# 01_POWER.net
KiCad netlist of a schematic drawn in Altium Designer
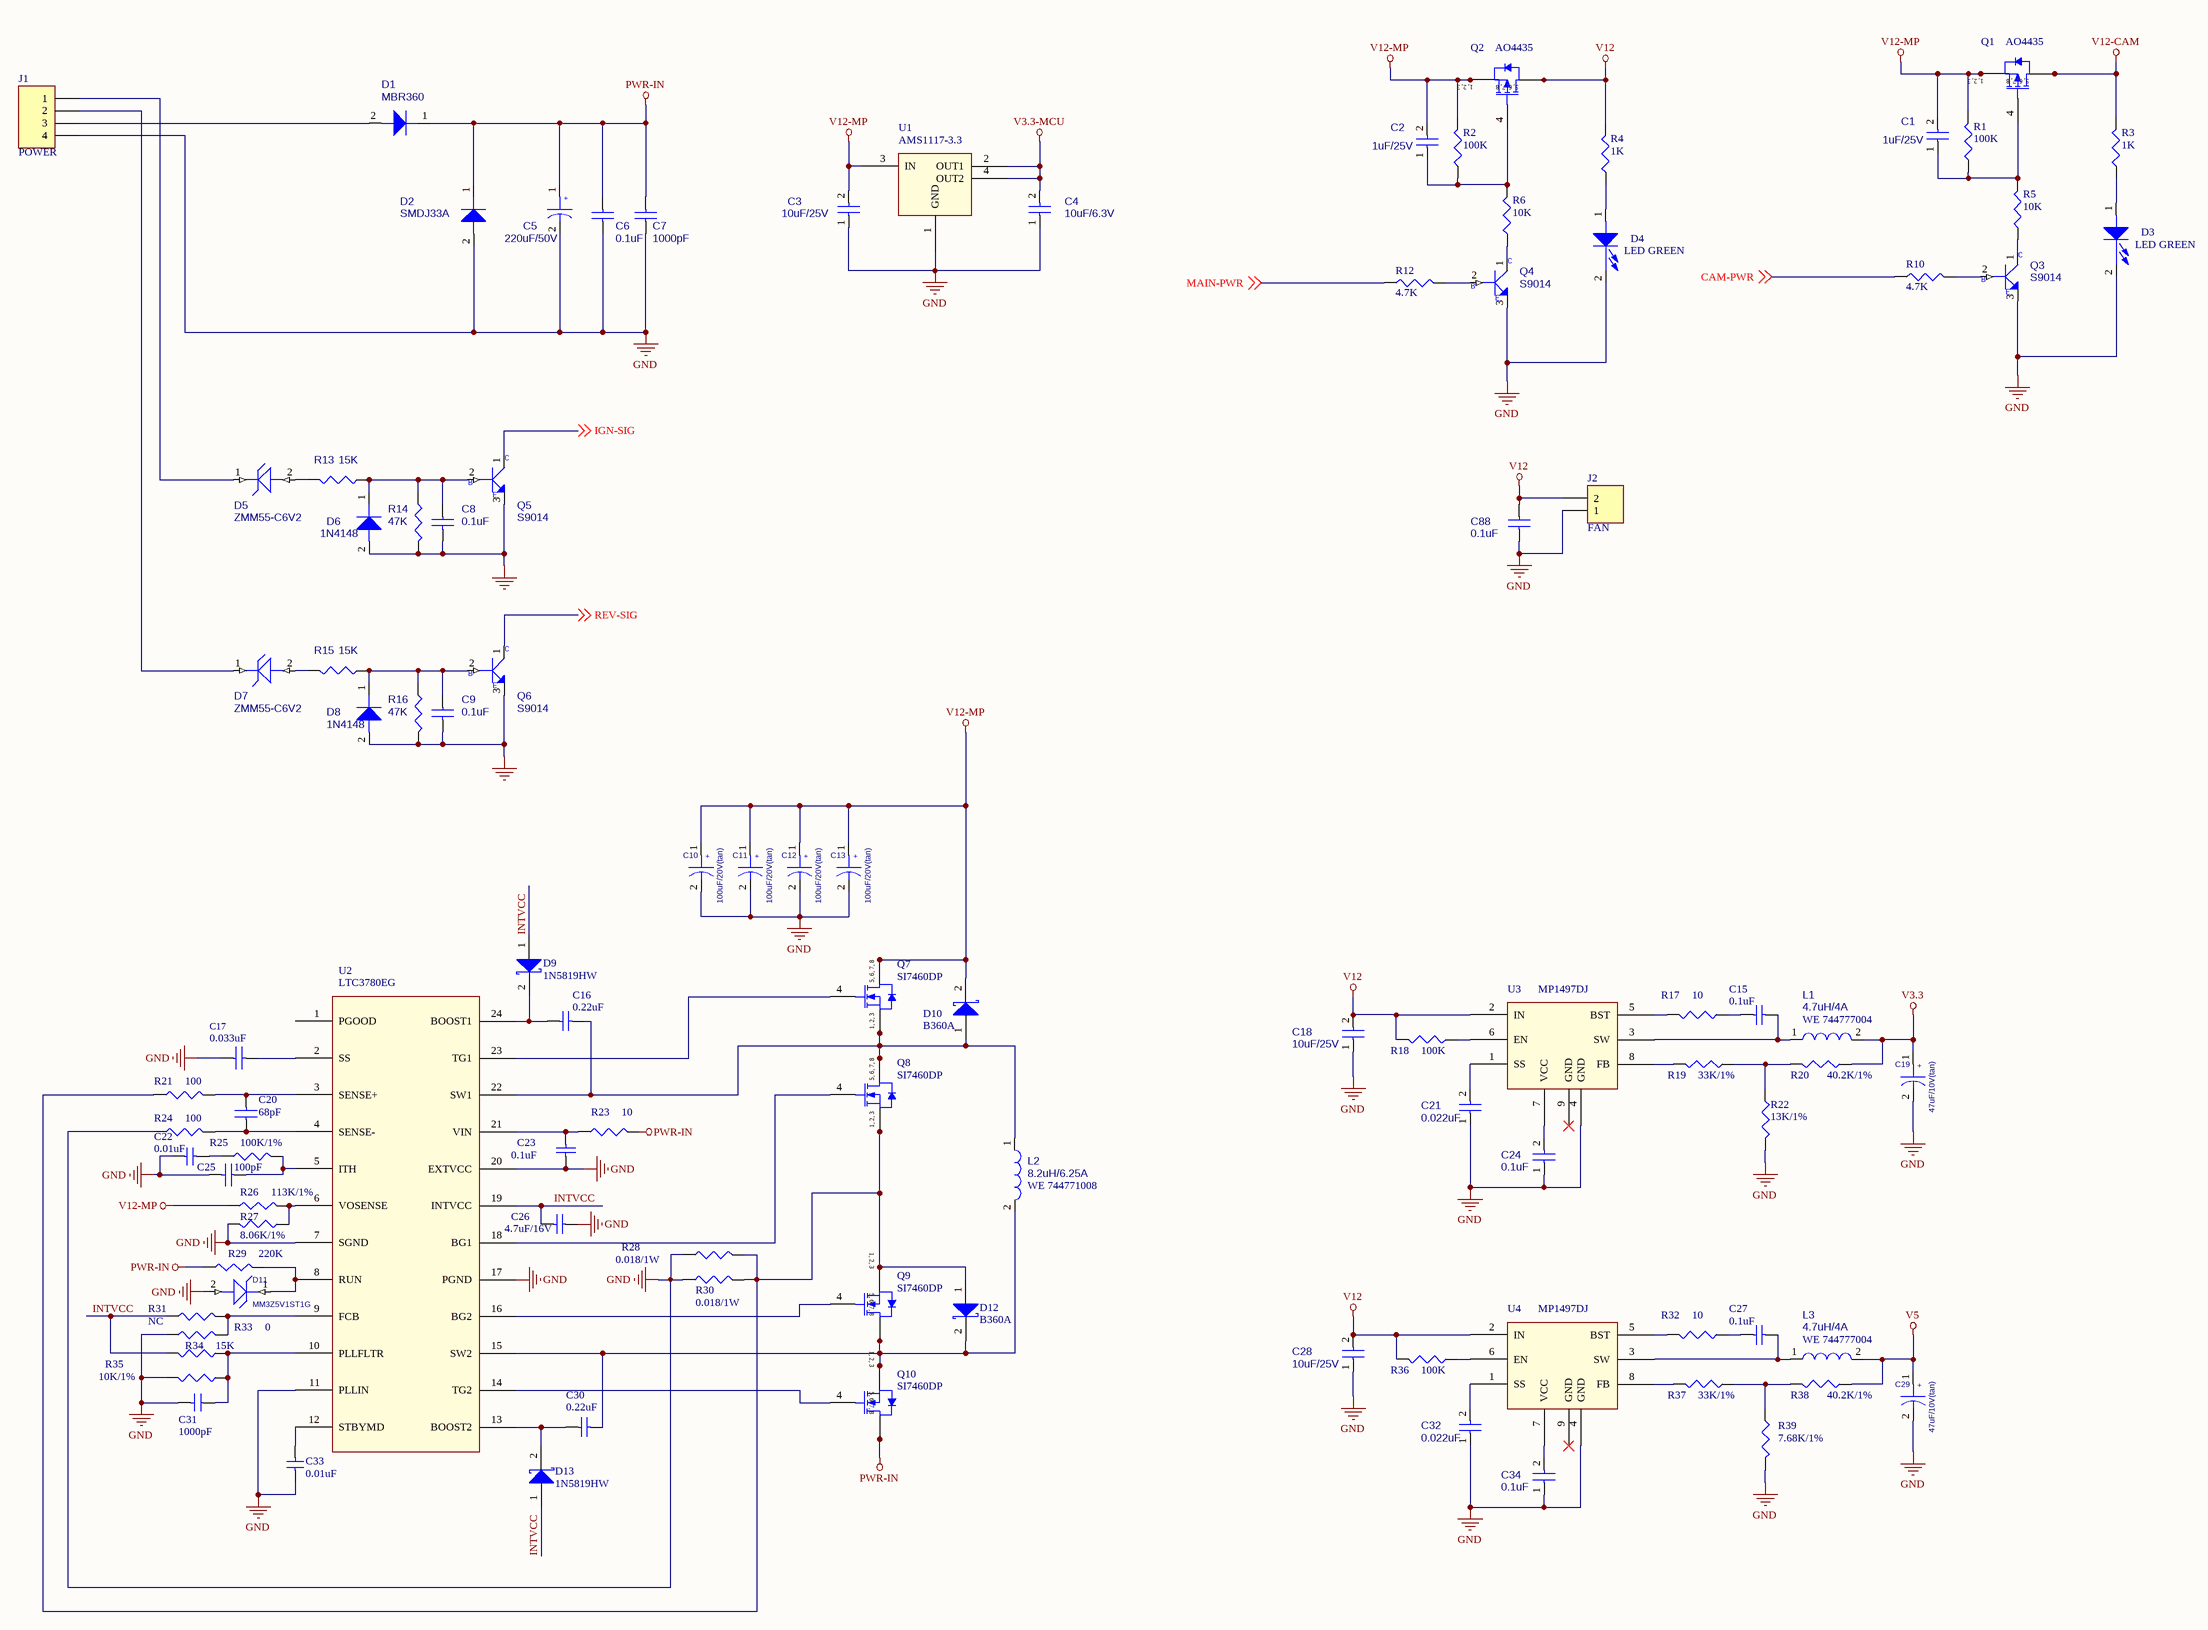
[diagram p0: [01]POWER.SchDoc]

(export (version "E")
  (design (tool "Eeschema 10.0.6"))
  (components
    (comp (ref "C1") (value "1uF/25V") (footprint "0805") (libsource (lib "*") (part "CAP NP_Dup2")))
    (comp (ref "C2") (value "1uF/25V") (footprint "0805") (libsource (lib "*") (part "CAP NP_Dup2")))
    (comp (ref "C3") (value "10uF/25V") (footprint "1812") (libsource (lib "*") (part "CAP NP_Dup2")))
    (comp (ref "C4") (value "10uF/6.3V") (footprint "0805") (libsource (lib "*") (part "CAP NP_Dup2")))
    (comp (ref "C5") (value "220uF/50V") (libsource (lib "*") (part "CAP WP")))
    (comp (ref "C6") (value "0.1uF") (libsource (lib "") (part "CAP NP_Dup2_1")))
    (comp (ref "C7") (value "1000pF") (libsource (lib "") (part "CAP NP_Dup2_1")))
    (comp (ref "C8") (value "0.1uF") (libsource (lib "*") (part "CAP")))
    (comp (ref "C9") (value "0.1uF") (libsource (lib "*") (part "CAP")))
    (comp (ref "C10") (value "100uF/20V(tan)") (footprint "7343") (libsource (lib "*") (part "CAP WP")))
    (comp (ref "C11") (value "100uF/20V(tan)") (footprint "7343") (libsource (lib "*") (part "CAP WP")))
    (comp (ref "C12") (value "100uF/20V(tan)") (footprint "7343") (libsource (lib "*") (part "CAP WP")))
    (comp (ref "C13") (value "100uF/20V(tan)") (footprint "7343") (libsource (lib "*") (part "CAP WP")))
    (comp (ref "C15")
      (value "0.1uF")
      (footprint "0603")
      (description "Capacitor")
      (libsource (lib "Miscellaneous Devices") (part "Cap"))
    )
    (comp (ref "C16")
      (value "0.22uF")
      (footprint "0603")
      (description "Capacitor")
      (libsource (lib "Miscellaneous Devices") (part "Cap"))
    )
    (comp (ref "C17") (value "0.033uF") (footprint "0603") (libsource (lib "*") (part "06033C223KAT1A_0")))
    (comp (ref "C18") (value "10uF/25V") (footprint "1812") (libsource (lib "*") (part "CAP NP_Dup2")))
    (comp (ref "C19") (value "47uF/10V(tan)") (footprint "3528") (libsource (lib "*") (part "CAP WP")))
    (comp (ref "C20") (value "68pF") (footprint "0603") (libsource (lib "*") (part "06033C223KAT1A_0")))
    (comp (ref "C21") (value "0.022uF") (footprint "0603") (libsource (lib "*") (part "CAP NP_Dup2")))
    (comp (ref "C22") (value "0.01uF") (footprint "0603") (libsource (lib "*") (part "06033C103KAT2A")))
    (comp (ref "C23")
      (value "0.1uF")
      (footprint "0603")
      (description "Capacitor")
      (libsource (lib "Miscellaneous Devices") (part "Cap"))
    )
    (comp (ref "C24") (value "0.1uF") (footprint "0603") (libsource (lib "*") (part "CAP NP_Dup2")))
    (comp (ref "C25") (value "100pF") (footprint "0603") (libsource (lib "*") (part "06035A470KAT1A_0")))
    (comp (ref "C26")
      (value "4.7uF/16V")
      (footprint "0805")
      (description "Capacitor")
      (libsource (lib "Miscellaneous Devices") (part "Cap"))
    )
    (comp (ref "C27")
      (value "0.1uF")
      (footprint "0603")
      (description "Capacitor")
      (libsource (lib "Miscellaneous Devices") (part "Cap"))
    )
    (comp (ref "C28") (value "10uF/25V") (footprint "1812") (libsource (lib "*") (part "CAP NP_Dup2")))
    (comp (ref "C29") (value "47uF/10V(tan)") (footprint "3528") (libsource (lib "*") (part "CAP WP")))
    (comp (ref "C30")
      (value "0.22uF")
      (footprint "0603")
      (description "Capacitor")
      (libsource (lib "Miscellaneous Devices") (part "Cap"))
    )
    (comp (ref "C31") (value "1000pF") (footprint "0603") (libsource (lib "*") (part "06033C103KAT2A_0")))
    (comp (ref "C32") (value "0.022uF") (footprint "0603") (libsource (lib "*") (part "CAP NP_Dup2")))
    (comp (ref "C33") (value "0.01uF") (footprint "0603") (libsource (lib "*") (part "06033C103KAT2A_0")))
    (comp (ref "C34") (value "0.1uF") (footprint "0603") (libsource (lib "*") (part "CAP NP_Dup2")))
    (comp (ref "C88") (value "0.1uF") (libsource (lib "") (part "CAP NP_Dup2_1")))
    (comp (ref "D1")
      (value "MBR360")
      (footprint "DO214AB")
      (libsource (lib "*") (part "1N4148WS-7-F_SOD323-2"))
    )
    (comp (ref "D2")
      (value "SMDJ33A")
      (footprint "DO214AB")
      (libsource (lib "*") (part "1N4148WS-7-F_SOD323-2"))
    )
    (comp (ref "D3") (value "LED GREEN") (footprint "LED0603") (libsource (lib "*") (part "LN01401_1")))
    (comp (ref "D4") (value "LED GREEN") (footprint "LED0603") (libsource (lib "*") (part "LN01401_1")))
    (comp (ref "D5")
      (value "ZMM55-C6V2")
      (footprint "MINI-MELF")
      (libsource (lib "*") (part "MMGZ5231BPTLL34"))
    )
    (comp (ref "D6")
      (value "1N4148")
      (footprint "MINI-MELF")
      (libsource (lib "*") (part "1N4148WS-7-F_SOD323-2"))
    )
    (comp (ref "D7")
      (value "ZMM55-C6V2")
      (footprint "MINI-MELF")
      (libsource (lib "*") (part "MMGZ5231BPTLL34"))
    )
    (comp (ref "D8")
      (value "1N4148")
      (footprint "MINI-MELF")
      (libsource (lib "*") (part "1N4148WS-7-F_SOD323-2"))
    )
    (comp (ref "D9")
      (value "1N5819HW")
      (footprint "1N5819")
      (description "Schottky Rectifier")
      (libsource (lib "Miscellaneous Devices") (part "Diode 11DQ03"))
    )
    (comp (ref "D10")
      (value "B360A")
      (footprint "B320A")
      (description "Schottky Rectifier")
      (libsource (lib "Miscellaneous Devices") (part "Diode 11DQ03"))
    )
    (comp (ref "D11")
      (value "MM3Z5V1ST1G")
      (footprint "MM3Z5V1ST1G")
      (libsource (lib "*") (part "MMGZ5231BPTLL34"))
    )
    (comp (ref "D12")
      (value "B360A")
      (footprint "B320A")
      (description "Schottky Rectifier")
      (libsource (lib "Miscellaneous Devices") (part "Diode 11DQ03"))
    )
    (comp (ref "D13")
      (value "1N5819HW")
      (footprint "1N5819")
      (description "Schottky Rectifier")
      (libsource (lib "Miscellaneous Devices") (part "Diode 11DQ03"))
    )
    (comp (ref "J1")
      (value "POWER")
      (footprint "5557-4PIN")
      (description "Header, 4-Pin")
      (libsource (lib "Miscellaneous Connectors") (part "Header 4"))
    )
    (comp (ref "J2")
      (value "FAN")
      (footprint "XH2.0-2P-SMD")
      (description "Header, 2-Pin")
      (fields (field (name "PUBLISHER") "Altium Limited"))
      (libsource (lib "Miscellaneous Connectors") (part "Header 2"))
    )
    (comp (ref "L1")
      (value "4.7uH/4A")
      (footprint "IND-4.7UH-4A")
      (fields (field (name "CODE") "WE 744777004"))
      (libsource (lib "*") (part "4.7UH_CDH2D09BNP-4R7MC_0.7A_20%"))
    )
    (comp (ref "L2")
      (value "8.2uH/6.25A")
      (footprint "IND-8.2UH-10A")
      (fields (field (name "CODE") "WE 744771008"))
      (libsource (lib "*") (part "4.7UH_CDH2D09BNP-4R7MC_0.7A_20%"))
    )
    (comp (ref "L3")
      (value "4.7uH/4A")
      (footprint "IND-4.7UH-4A")
      (fields (field (name "CODE") "WE 744777004"))
      (libsource (lib "*") (part "4.7UH_CDH2D09BNP-4R7MC_0.7A_20%"))
    )
    (comp (ref "Q1")
      (value "AO4435")
      (footprint "SO8")
      (description "P-Channel 30V (D-S)  MOSFET")
      (fields (field (name "PUBLISHER") "Altium Limited"))
      (libsource (lib "Vishay Siliconix Discrete MOSFET") (part "SI4431DY"))
    )
    (comp (ref "Q2")
      (value "AO4435")
      (footprint "SO8")
      (description "P-Channel 30V (D-S)  MOSFET")
      (fields (field (name "PUBLISHER") "Altium Limited"))
      (libsource (lib "Vishay Siliconix Discrete MOSFET") (part "SI4431DY"))
    )
    (comp (ref "Q3")
      (value "S9014")
      (footprint "NPN")
      (fields (field (name "PART NUMBER") "SB039040000"))
      (libsource (lib "*") (part "MMBT3904_NL_SOT23-3"))
    )
    (comp (ref "Q4")
      (value "S9014")
      (footprint "NPN")
      (fields (field (name "PART NUMBER") "SB039040000"))
      (libsource (lib "*") (part "MMBT3904_NL_SOT23-3"))
    )
    (comp (ref "Q5")
      (value "S9014")
      (footprint "NPN")
      (fields (field (name "PART NUMBER") "SB039040000"))
      (libsource (lib "*") (part "MMBT3904_NL_SOT23-3"))
    )
    (comp (ref "Q6") (value "S9014") (footprint "NPN") (libsource (lib "*") (part "MMBT3904_NL_SOT23-3")))
    (comp (ref "Q7")
      (value "SI7460DP")
      (footprint "POWERPAK")
      (description "N-Channel 30V (D-S)  MOSFET")
      (libsource (lib "Vishay Siliconix Discrete MOSFET") (part "SI4410DY"))
    )
    (comp (ref "Q8")
      (value "SI7460DP")
      (footprint "POWERPAK")
      (description "N-Channel 30V (D-S)  MOSFET")
      (libsource (lib "Vishay Siliconix Discrete MOSFET") (part "SI4410DY"))
    )
    (comp (ref "Q9")
      (value "SI7460DP")
      (footprint "POWERPAK")
      (description "N-Channel 30V (D-S)  MOSFET")
      (libsource (lib "Vishay Siliconix Discrete MOSFET") (part "SI4410DY"))
    )
    (comp (ref "Q10")
      (value "SI7460DP")
      (footprint "POWERPAK")
      (description "N-Channel 30V (D-S)  MOSFET")
      (libsource (lib "Vishay Siliconix Discrete MOSFET") (part "SI4410DY"))
    )
    (comp (ref "R1") (value "100K") (footprint "0603") (libsource (lib "*") (part "CR16-1003FM")))
    (comp (ref "R2") (value "100K") (footprint "0603") (libsource (lib "*") (part "CR16-1003FM")))
    (comp (ref "R3") (value "1K") (footprint "0603") (libsource (lib "*") (part "CR16-1003FM")))
    (comp (ref "R4") (value "1K") (footprint "0603") (libsource (lib "*") (part "CR16-1003FM")))
    (comp (ref "R5") (value "10K") (footprint "0603") (libsource (lib "*") (part "CR16-1003FM")))
    (comp (ref "R6") (value "10K") (footprint "0603") (libsource (lib "*") (part "CR16-1003FM")))
    (comp (ref "R10") (value "4.7K") (footprint "0603") (libsource (lib "*") (part "CR16-1003FM")))
    (comp (ref "R12") (value "4.7K") (footprint "0603") (libsource (lib "*") (part "CR16-1003FM")))
    (comp (ref "R13") (value "15K") (libsource (lib "*") (part "R")))
    (comp (ref "R14") (value "47K") (libsource (lib "*") (part "R")))
    (comp (ref "R15") (value "15K") (libsource (lib "*") (part "R")))
    (comp (ref "R16") (value "47K") (libsource (lib "*") (part "R")))
    (comp (ref "R17") (value "10") (footprint "0603") (libsource (lib "*") (part "CR16-1003FM")))
    (comp (ref "R18") (value "100K") (footprint "0603") (libsource (lib "*") (part "CR16-1003FM")))
    (comp (ref "R19") (value "33K/1%") (footprint "0603") (libsource (lib "*") (part "CR16-1003FM")))
    (comp (ref "R20") (value "40.2K/1%") (footprint "0603") (libsource (lib "*") (part "CR16-1003FM")))
    (comp (ref "R21") (value "100") (footprint "0603") (libsource (lib "*") (part "CR16-1241FM")))
    (comp (ref "R22") (value "13K/1%") (footprint "0603") (libsource (lib "*") (part "CR16-1003FM")))
    (comp (ref "R23") (value "10") (footprint "0603") (libsource (lib "*") (part "CR16-1003FM")))
    (comp (ref "R24") (value "100") (footprint "0603") (libsource (lib "*") (part "CR16-1241FM")))
    (comp (ref "R25") (value "100K/1%") (footprint "0603") (libsource (lib "*") (part "CR16-1003FM")))
    (comp (ref "R26") (value "113K/1%") (footprint "0603") (libsource (lib "*") (part "CR16-1133FM")))
    (comp (ref "R27") (value "8.06K/1%") (footprint "0603") (libsource (lib "*") (part "CR16-8061FM")))
    (comp (ref "R28") (value "0.018/1W") (footprint "2512") (libsource (lib "*") (part "CR16-1003FM")))
    (comp (ref "R29") (value "220K") (footprint "0603") (libsource (lib "*") (part "CR16-224JM")))
    (comp (ref "R30") (value "0.018/1W") (footprint "2512") (libsource (lib "*") (part "CR16-1003FM")))
    (comp (ref "R31") (value "NC") (footprint "0603") (libsource (lib "*") (part "CR16-1003FM")))
    (comp (ref "R32") (value "10") (footprint "0603") (libsource (lib "*") (part "CR16-1003FM")))
    (comp (ref "R33") (value "0") (footprint "0603") (libsource (lib "*") (part "CR16-1003FM")))
    (comp (ref "R34") (value "15K") (footprint "0603") (libsource (lib "*") (part "CR16-1003FM")))
    (comp (ref "R35") (value "10K/1%") (footprint "0603") (libsource (lib "*") (part "CR16-1003FM")))
    (comp (ref "R36") (value "100K") (footprint "0603") (libsource (lib "*") (part "CR16-1003FM")))
    (comp (ref "R37") (value "33K/1%") (footprint "0603") (libsource (lib "*") (part "CR16-1003FM")))
    (comp (ref "R38") (value "40.2K/1%") (footprint "0603") (libsource (lib "*") (part "CR16-1003FM")))
    (comp (ref "R39") (value "7.68K/1%") (footprint "0603") (libsource (lib "*") (part "CR16-1003FM")))
    (comp (ref "U1")
      (value "AMS1117-3.3")
      (footprint "AMS1117")
      (libsource (lib "*") (part "LT1963EST-1_4.8"))
    )
    (comp (ref "U2") (value "LTC3780EG") (footprint "LTC3780EG") (libsource (lib "*") (part "LTC3780EG")))
    (comp (ref "U3") (value "MP1497DJ") (footprint "TSOT23-8") (libsource (lib "*") (part "MP1482_5")))
    (comp (ref "U4") (value "MP1497DJ") (footprint "TSOT23-8") (libsource (lib "*") (part "MP1482_5")))
  )
  (nets
    (net (code "1") (name "/INTVCC") (class "Default")
      (node (ref "C26") (pin "1") (pinfunction "1_1") (pintype "passive"))
      (node (ref "D13") (pin "1") (pinfunction "A_1") (pintype "passive"))
      (node (ref "D9") (pin "1") (pinfunction "A_1") (pintype "passive"))
      (node (ref "R31") (pin "1") (pinfunction "1_1") (pintype "passive"))
      (node (ref "R34") (pin "2") (pinfunction "2_2") (pintype "passive"))
      (node (ref "U2") (pin "19") (pinfunction "INTVCC_19") (pintype "passive"))
    )
    (net (code "2") (name "CAM-PWR") (class "Default")
      (node (ref "R10") (pin "1") (pinfunction "1_1") (pintype "passive"))
    )
    (net (code "3") (name "GND") (class "Default")
      (node (ref "C10") (pin "2") (pinfunction "2_2") (pintype "passive"))
      (node (ref "C11") (pin "2") (pinfunction "2_2") (pintype "passive"))
      (node (ref "C12") (pin "2") (pinfunction "2_2") (pintype "passive"))
      (node (ref "C13") (pin "2") (pinfunction "2_2") (pintype "passive"))
      (node (ref "C17") (pin "1") (pinfunction "1_1") (pintype "passive"))
      (node (ref "C18") (pin "1") (pinfunction "1_1") (pintype "passive"))
      (node (ref "C19") (pin "2") (pinfunction "2_2") (pintype "passive"))
      (node (ref "C21") (pin "1") (pinfunction "1_1") (pintype "passive"))
      (node (ref "C22") (pin "1") (pinfunction "1_1") (pintype "passive"))
      (node (ref "C23") (pin "1") (pinfunction "1_1") (pintype "passive"))
      (node (ref "C24") (pin "1") (pinfunction "1_1") (pintype "passive"))
      (node (ref "C25") (pin "2") (pinfunction "2_2") (pintype "passive"))
      (node (ref "C26") (pin "2") (pinfunction "2_2") (pintype "passive"))
      (node (ref "C28") (pin "1") (pinfunction "1_1") (pintype "passive"))
      (node (ref "C29") (pin "2") (pinfunction "2_2") (pintype "passive"))
      (node (ref "C3") (pin "1") (pinfunction "1_1") (pintype "passive"))
      (node (ref "C31") (pin "2") (pinfunction "2_2") (pintype "passive"))
      (node (ref "C32") (pin "1") (pinfunction "1_1") (pintype "passive"))
      (node (ref "C33") (pin "1") (pinfunction "1_1") (pintype "passive"))
      (node (ref "C34") (pin "1") (pinfunction "1_1") (pintype "passive"))
      (node (ref "C4") (pin "1") (pinfunction "1_1") (pintype "passive"))
      (node (ref "C5") (pin "2") (pinfunction "2_2") (pintype "passive"))
      (node (ref "C6") (pin "1") (pinfunction "1_1") (pintype "passive"))
      (node (ref "C7") (pin "1") (pinfunction "1_1") (pintype "passive"))
      (node (ref "C8") (pin "2") (pinfunction "2_2") (pintype "passive"))
      (node (ref "C88") (pin "1") (pinfunction "1_1") (pintype "passive"))
      (node (ref "C9") (pin "2") (pinfunction "2_2") (pintype "passive"))
      (node (ref "D11") (pin "2") (pinfunction "2_2") (pintype "input"))
      (node (ref "D2") (pin "2") (pinfunction "2_2") (pintype "passive"))
      (node (ref "D3") (pin "2") (pinfunction "CATHODE_2") (pintype "passive"))
      (node (ref "D4") (pin "2") (pinfunction "CATHODE_2") (pintype "passive"))
      (node (ref "D6") (pin "2") (pinfunction "2_2") (pintype "passive"))
      (node (ref "D8") (pin "2") (pinfunction "2_2") (pintype "passive"))
      (node (ref "J1") (pin "4") (pinfunction "4_4") (pintype "passive"))
      (node (ref "J2") (pin "1") (pinfunction "1_1") (pintype "passive"))
      (node (ref "Q3") (pin "3") (pinfunction "EMITTER_3") (pintype "passive"))
      (node (ref "Q4") (pin "3") (pinfunction "EMITTER_3") (pintype "passive"))
      (node (ref "Q5") (pin "3") (pinfunction "EMITTER_3") (pintype "passive"))
      (node (ref "Q6") (pin "3") (pinfunction "EMITTER_3") (pintype "passive"))
      (node (ref "R14") (pin "2") (pinfunction "2_2") (pintype "passive"))
      (node (ref "R16") (pin "2") (pinfunction "2_2") (pintype "passive"))
      (node (ref "R22") (pin "2") (pinfunction "2_2") (pintype "passive"))
      (node (ref "R24") (pin "1") (pinfunction "1_1") (pintype "passive"))
      (node (ref "R27") (pin "2") (pinfunction "2_2") (pintype "passive"))
      (node (ref "R28") (pin "1") (pinfunction "1_1") (pintype "passive"))
      (node (ref "R30") (pin "1") (pinfunction "1_1") (pintype "passive"))
      (node (ref "R33") (pin "1") (pinfunction "1_1") (pintype "passive"))
      (node (ref "R35") (pin "2") (pinfunction "2_2") (pintype "passive"))
      (node (ref "R39") (pin "2") (pinfunction "2_2") (pintype "passive"))
      (node (ref "U1") (pin "1") (pinfunction "GND_1") (pintype "passive"))
      (node (ref "U2") (pin "11") (pinfunction "PLLIN_11") (pintype "passive"))
      (node (ref "U2") (pin "17") (pinfunction "PGND_17") (pintype "passive"))
      (node (ref "U2") (pin "20") (pinfunction "EXTVCC_20") (pintype "passive"))
      (node (ref "U2") (pin "7") (pinfunction "SGND_7") (pintype "passive"))
      (node (ref "U3") (pin "4") (pinfunction "GND_4") (pintype "power_in"))
      (node (ref "U4") (pin "4") (pinfunction "GND_4") (pintype "power_in"))
    )
    (net (code "4") (name "IGN-SIG") (class "Default")
      (node (ref "Q5") (pin "1") (pinfunction "COLLECTOR_1") (pintype "passive"))
    )
    (net (code "5") (name "MAIN-PWR") (class "Default")
      (node (ref "R12") (pin "1") (pinfunction "1_1") (pintype "passive"))
    )
    (net (code "6") (name "Net-(C15-Pad2)") (class "Default")
      (node (ref "C15") (pin "2") (pinfunction "2_2") (pintype "passive"))
      (node (ref "R17") (pin "1") (pinfunction "1_1") (pintype "passive"))
    )
    (net (code "7") (name "Net-(C22-Pad2)") (class "Default")
      (node (ref "C22") (pin "2") (pinfunction "2_2") (pintype "passive"))
      (node (ref "R25") (pin "1") (pinfunction "1_1") (pintype "passive"))
    )
    (net (code "8") (name "Net-(C27-Pad2)") (class "Default")
      (node (ref "C27") (pin "2") (pinfunction "2_2") (pintype "passive"))
      (node (ref "R32") (pin "1") (pinfunction "1_1") (pintype "passive"))
    )
    (net (code "9") (name "Net-(D1-Pad2)") (class "Default")
      (node (ref "D1") (pin "2") (pinfunction "2_2") (pintype "passive"))
      (node (ref "J1") (pin "3") (pinfunction "3_3") (pintype "passive"))
    )
    (net (code "10") (name "Net-(D3-ANODE)") (class "Default")
      (node (ref "D3") (pin "1") (pinfunction "ANODE_1") (pintype "passive"))
      (node (ref "R3") (pin "1") (pinfunction "1_1") (pintype "passive"))
    )
    (net (code "11") (name "Net-(D4-ANODE)") (class "Default")
      (node (ref "D4") (pin "1") (pinfunction "ANODE_1") (pintype "passive"))
      (node (ref "R4") (pin "1") (pinfunction "1_1") (pintype "passive"))
    )
    (net (code "12") (name "Net-(D5-Pad1)") (class "Default")
      (node (ref "D5") (pin "1") (pinfunction "1_1") (pintype "input"))
      (node (ref "J1") (pin "1") (pinfunction "1_1") (pintype "passive"))
    )
    (net (code "13") (name "Net-(D5-Pad2)") (class "Default")
      (node (ref "D5") (pin "2") (pinfunction "2_2") (pintype "input"))
      (node (ref "R13") (pin "2") (pinfunction "2_2") (pintype "passive"))
    )
    (net (code "14") (name "Net-(D7-Pad1)") (class "Default")
      (node (ref "D7") (pin "1") (pinfunction "1_1") (pintype "input"))
      (node (ref "J1") (pin "2") (pinfunction "2_2") (pintype "passive"))
    )
    (net (code "15") (name "Net-(D7-Pad2)") (class "Default")
      (node (ref "D7") (pin "2") (pinfunction "2_2") (pintype "input"))
      (node (ref "R15") (pin "2") (pinfunction "2_2") (pintype "passive"))
    )
    (net (code "16") (name "Net-(D9-K)") (class "Default")
      (node (ref "C16") (pin "2") (pinfunction "2_2") (pintype "passive"))
      (node (ref "D9") (pin "2") (pinfunction "K_2") (pintype "passive"))
      (node (ref "U2") (pin "24") (pinfunction "BOOST1_24") (pintype "passive"))
    )
    (net (code "17") (name "Net-(D10-A)") (class "Default")
      (node (ref "C16") (pin "1") (pinfunction "1_1") (pintype "passive"))
      (node (ref "D10") (pin "1") (pinfunction "A_1") (pintype "passive"))
      (node (ref "L2") (pin "1") (pinfunction "1_1") (pintype "passive"))
      (node (ref "Q7") (pin "1") (pinfunction "S_1") (pintype "passive"))
      (node (ref "Q7") (pin "2") (pinfunction "S_2") (pintype "passive"))
      (node (ref "Q7") (pin "3") (pinfunction "S_3") (pintype "passive"))
      (node (ref "Q8") (pin "5") (pinfunction "D_5") (pintype "passive"))
      (node (ref "Q8") (pin "6") (pinfunction "D_6") (pintype "passive"))
      (node (ref "Q8") (pin "7") (pinfunction "D_7") (pintype "passive"))
      (node (ref "Q8") (pin "8") (pinfunction "D_8") (pintype "passive"))
      (node (ref "U2") (pin "22") (pinfunction "SW1_22") (pintype "passive"))
    )
    (net (code "18") (name "Net-(D12-A)") (class "Default")
      (node (ref "D12") (pin "1") (pinfunction "A_1") (pintype "passive"))
      (node (ref "Q8") (pin "1") (pinfunction "S_1") (pintype "passive"))
      (node (ref "Q8") (pin "2") (pinfunction "S_2") (pintype "passive"))
      (node (ref "Q8") (pin "3") (pinfunction "S_3") (pintype "passive"))
      (node (ref "Q9") (pin "1") (pinfunction "S_1") (pintype "passive"))
      (node (ref "Q9") (pin "2") (pinfunction "S_2") (pintype "passive"))
      (node (ref "Q9") (pin "3") (pinfunction "S_3") (pintype "passive"))
      (node (ref "R21") (pin "1") (pinfunction "1_1") (pintype "passive"))
      (node (ref "R28") (pin "2") (pinfunction "2_2") (pintype "passive"))
      (node (ref "R30") (pin "2") (pinfunction "2_2") (pintype "passive"))
    )
    (net (code "19") (name "Net-(D12-K)") (class "Default")
      (node (ref "C30") (pin "1") (pinfunction "1_1") (pintype "passive"))
      (node (ref "D12") (pin "2") (pinfunction "K_2") (pintype "passive"))
      (node (ref "L2") (pin "2") (pinfunction "2_2") (pintype "passive"))
      (node (ref "Q10") (pin "1") (pinfunction "S_1") (pintype "passive"))
      (node (ref "Q10") (pin "2") (pinfunction "S_2") (pintype "passive"))
      (node (ref "Q10") (pin "3") (pinfunction "S_3") (pintype "passive"))
      (node (ref "Q9") (pin "5") (pinfunction "D_5") (pintype "passive"))
      (node (ref "Q9") (pin "6") (pinfunction "D_6") (pintype "passive"))
      (node (ref "Q9") (pin "7") (pinfunction "D_7") (pintype "passive"))
      (node (ref "Q9") (pin "8") (pinfunction "D_8") (pintype "passive"))
      (node (ref "U2") (pin "15") (pinfunction "SW2_15") (pintype "passive"))
    )
    (net (code "20") (name "Net-(D13-K)") (class "Default")
      (node (ref "C30") (pin "2") (pinfunction "2_2") (pintype "passive"))
      (node (ref "D13") (pin "2") (pinfunction "K_2") (pintype "passive"))
      (node (ref "U2") (pin "13") (pinfunction "BOOST2_13") (pintype "passive"))
    )
    (net (code "21") (name "Net-(Q1-G)") (class "Default")
      (node (ref "C1") (pin "1") (pinfunction "1_1") (pintype "passive"))
      (node (ref "Q1") (pin "4") (pinfunction "G_4") (pintype "passive"))
      (node (ref "R1") (pin "1") (pinfunction "1_1") (pintype "passive"))
      (node (ref "R5") (pin "2") (pinfunction "2_2") (pintype "passive"))
    )
    (net (code "22") (name "Net-(Q2-G)") (class "Default")
      (node (ref "C2") (pin "1") (pinfunction "1_1") (pintype "passive"))
      (node (ref "Q2") (pin "4") (pinfunction "G_4") (pintype "passive"))
      (node (ref "R2") (pin "1") (pinfunction "1_1") (pintype "passive"))
      (node (ref "R6") (pin "2") (pinfunction "2_2") (pintype "passive"))
    )
    (net (code "23") (name "Net-(Q3-BASE)") (class "Default")
      (node (ref "Q3") (pin "2") (pinfunction "BASE_2") (pintype "input"))
      (node (ref "R10") (pin "2") (pinfunction "2_2") (pintype "passive"))
    )
    (net (code "24") (name "Net-(Q3-COLLECTOR)") (class "Default")
      (node (ref "Q3") (pin "1") (pinfunction "COLLECTOR_1") (pintype "passive"))
      (node (ref "R5") (pin "1") (pinfunction "1_1") (pintype "passive"))
    )
    (net (code "25") (name "Net-(Q4-BASE)") (class "Default")
      (node (ref "Q4") (pin "2") (pinfunction "BASE_2") (pintype "input"))
      (node (ref "R12") (pin "2") (pinfunction "2_2") (pintype "passive"))
    )
    (net (code "26") (name "Net-(Q4-COLLECTOR)") (class "Default")
      (node (ref "Q4") (pin "1") (pinfunction "COLLECTOR_1") (pintype "passive"))
      (node (ref "R6") (pin "1") (pinfunction "1_1") (pintype "passive"))
    )
    (net (code "27") (name "Net-(Q5-BASE)") (class "Default")
      (node (ref "C8") (pin "1") (pinfunction "1_1") (pintype "passive"))
      (node (ref "D6") (pin "1") (pinfunction "1_1") (pintype "passive"))
      (node (ref "Q5") (pin "2") (pinfunction "BASE_2") (pintype "input"))
      (node (ref "R13") (pin "1") (pinfunction "1_1") (pintype "passive"))
      (node (ref "R14") (pin "1") (pinfunction "1_1") (pintype "passive"))
    )
    (net (code "28") (name "Net-(Q6-BASE)") (class "Default")
      (node (ref "C9") (pin "1") (pinfunction "1_1") (pintype "passive"))
      (node (ref "D8") (pin "1") (pinfunction "1_1") (pintype "passive"))
      (node (ref "Q6") (pin "2") (pinfunction "BASE_2") (pintype "input"))
      (node (ref "R15") (pin "1") (pinfunction "1_1") (pintype "passive"))
      (node (ref "R16") (pin "1") (pinfunction "1_1") (pintype "passive"))
    )
    (net (code "29") (name "Net-(Q7-G)") (class "Default")
      (node (ref "Q7") (pin "4") (pinfunction "G_4") (pintype "passive"))
      (node (ref "U2") (pin "23") (pinfunction "TG1_23") (pintype "passive"))
    )
    (net (code "30") (name "Net-(Q8-G)") (class "Default")
      (node (ref "Q8") (pin "4") (pinfunction "G_4") (pintype "passive"))
      (node (ref "U2") (pin "18") (pinfunction "BG1_18") (pintype "passive"))
    )
    (net (code "31") (name "Net-(Q9-G)") (class "Default")
      (node (ref "Q9") (pin "4") (pinfunction "G_4") (pintype "passive"))
      (node (ref "U2") (pin "16") (pinfunction "BG2_16") (pintype "passive"))
    )
    (net (code "32") (name "Net-(Q10-G)") (class "Default")
      (node (ref "Q10") (pin "4") (pinfunction "G_4") (pintype "passive"))
      (node (ref "U2") (pin "14") (pinfunction "TG2_14") (pintype "passive"))
    )
    (net (code "33") (name "Net-(R19-Pad1)") (class "Default")
      (node (ref "R19") (pin "1") (pinfunction "1_1") (pintype "passive"))
      (node (ref "R20") (pin "2") (pinfunction "2_2") (pintype "passive"))
      (node (ref "R22") (pin "1") (pinfunction "1_1") (pintype "passive"))
    )
    (net (code "34") (name "Net-(R37-Pad1)") (class "Default")
      (node (ref "R37") (pin "1") (pinfunction "1_1") (pintype "passive"))
      (node (ref "R38") (pin "2") (pinfunction "2_2") (pintype "passive"))
      (node (ref "R39") (pin "1") (pinfunction "1_1") (pintype "passive"))
    )
    (net (code "35") (name "Net-(U2-FCB)") (class "Default")
      (node (ref "R31") (pin "2") (pinfunction "2_2") (pintype "passive"))
      (node (ref "R33") (pin "2") (pinfunction "2_2") (pintype "passive"))
      (node (ref "U2") (pin "9") (pinfunction "FCB_9") (pintype "passive"))
    )
    (net (code "36") (name "Net-(U2-ITH)") (class "Default")
      (node (ref "C25") (pin "1") (pinfunction "1_1") (pintype "passive"))
      (node (ref "R25") (pin "2") (pinfunction "2_2") (pintype "passive"))
      (node (ref "U2") (pin "5") (pinfunction "ITH_5") (pintype "passive"))
    )
    (net (code "37") (name "Net-(U2-PLLFLTR)") (class "Default")
      (node (ref "C31") (pin "1") (pinfunction "1_1") (pintype "passive"))
      (node (ref "R34") (pin "1") (pinfunction "1_1") (pintype "passive"))
      (node (ref "R35") (pin "1") (pinfunction "1_1") (pintype "passive"))
      (node (ref "U2") (pin "10") (pinfunction "PLLFLTR_10") (pintype "passive"))
    )
    (net (code "38") (name "Net-(U2-RUN)") (class "Default")
      (node (ref "D11") (pin "1") (pinfunction "1_1") (pintype "input"))
      (node (ref "R29") (pin "2") (pinfunction "2_2") (pintype "passive"))
      (node (ref "U2") (pin "8") (pinfunction "RUN_8") (pintype "passive"))
    )
    (net (code "39") (name "Net-(U2-SENSE+)") (class "Default")
      (node (ref "C20") (pin "2") (pinfunction "2_2") (pintype "passive"))
      (node (ref "R21") (pin "2") (pinfunction "2_2") (pintype "passive"))
      (node (ref "U2") (pin "3") (pinfunction "SENSE+_3") (pintype "passive"))
    )
    (net (code "40") (name "Net-(U2-SENSE-)") (class "Default")
      (node (ref "C20") (pin "1") (pinfunction "1_1") (pintype "passive"))
      (node (ref "R24") (pin "2") (pinfunction "2_2") (pintype "passive"))
      (node (ref "U2") (pin "4") (pinfunction "SENSE-_4") (pintype "passive"))
    )
    (net (code "41") (name "Net-(U2-SS)") (class "Default")
      (node (ref "C17") (pin "2") (pinfunction "2_2") (pintype "passive"))
      (node (ref "U2") (pin "2") (pinfunction "SS_2") (pintype "passive"))
    )
    (net (code "42") (name "Net-(U2-STBYMD)") (class "Default")
      (node (ref "C33") (pin "2") (pinfunction "2_2") (pintype "passive"))
      (node (ref "U2") (pin "12") (pinfunction "STBYMD_12") (pintype "passive"))
    )
    (net (code "43") (name "Net-(U2-VIN)") (class "Default")
      (node (ref "C23") (pin "2") (pinfunction "2_2") (pintype "passive"))
      (node (ref "R23") (pin "1") (pinfunction "1_1") (pintype "passive"))
      (node (ref "U2") (pin "21") (pinfunction "VIN_21") (pintype "passive"))
    )
    (net (code "44") (name "Net-(U2-VOSENSE)") (class "Default")
      (node (ref "R26") (pin "2") (pinfunction "2_2") (pintype "passive"))
      (node (ref "R27") (pin "1") (pinfunction "1_1") (pintype "passive"))
      (node (ref "U2") (pin "6") (pinfunction "VOSENSE_6") (pintype "passive"))
    )
    (net (code "45") (name "Net-(U3-BST)") (class "Default")
      (node (ref "R17") (pin "2") (pinfunction "2_2") (pintype "passive"))
      (node (ref "U3") (pin "5") (pinfunction "BST_5") (pintype "passive"))
    )
    (net (code "46") (name "Net-(U3-EN)") (class "Default")
      (node (ref "R18") (pin "1") (pinfunction "1_1") (pintype "passive"))
      (node (ref "U3") (pin "6") (pinfunction "EN_6") (pintype "passive"))
    )
    (net (code "47") (name "Net-(U3-FB)") (class "Default")
      (node (ref "R19") (pin "2") (pinfunction "2_2") (pintype "passive"))
      (node (ref "U3") (pin "8") (pinfunction "FB_8") (pintype "passive"))
    )
    (net (code "48") (name "Net-(U3-SS)") (class "Default")
      (node (ref "C21") (pin "2") (pinfunction "2_2") (pintype "passive"))
      (node (ref "U3") (pin "1") (pinfunction "SS_1") (pintype "passive"))
    )
    (net (code "49") (name "Net-(U3-SW)") (class "Default")
      (node (ref "C15") (pin "1") (pinfunction "1_1") (pintype "passive"))
      (node (ref "L1") (pin "1") (pinfunction "1_1") (pintype "passive"))
      (node (ref "U3") (pin "3") (pinfunction "SW_3") (pintype "passive"))
    )
    (net (code "50") (name "Net-(U3-VCC)") (class "Default")
      (node (ref "C24") (pin "2") (pinfunction "2_2") (pintype "passive"))
      (node (ref "U3") (pin "7") (pinfunction "VCC_7") (pintype "passive"))
    )
    (net (code "51") (name "Net-(U4-BST)") (class "Default")
      (node (ref "R32") (pin "2") (pinfunction "2_2") (pintype "passive"))
      (node (ref "U4") (pin "5") (pinfunction "BST_5") (pintype "passive"))
    )
    (net (code "52") (name "Net-(U4-EN)") (class "Default")
      (node (ref "R36") (pin "1") (pinfunction "1_1") (pintype "passive"))
      (node (ref "U4") (pin "6") (pinfunction "EN_6") (pintype "passive"))
    )
    (net (code "53") (name "Net-(U4-FB)") (class "Default")
      (node (ref "R37") (pin "2") (pinfunction "2_2") (pintype "passive"))
      (node (ref "U4") (pin "8") (pinfunction "FB_8") (pintype "passive"))
    )
    (net (code "54") (name "Net-(U4-SS)") (class "Default")
      (node (ref "C32") (pin "2") (pinfunction "2_2") (pintype "passive"))
      (node (ref "U4") (pin "1") (pinfunction "SS_1") (pintype "passive"))
    )
    (net (code "55") (name "Net-(U4-SW)") (class "Default")
      (node (ref "C27") (pin "1") (pinfunction "1_1") (pintype "passive"))
      (node (ref "L3") (pin "1") (pinfunction "1_1") (pintype "passive"))
      (node (ref "U4") (pin "3") (pinfunction "SW_3") (pintype "passive"))
    )
    (net (code "56") (name "Net-(U4-VCC)") (class "Default")
      (node (ref "C34") (pin "2") (pinfunction "2_2") (pintype "passive"))
      (node (ref "U4") (pin "7") (pinfunction "VCC_7") (pintype "passive"))
    )
    (net (code "57") (name "PWR-IN") (class "Default")
      (node (ref "C5") (pin "1") (pinfunction "1_1") (pintype "passive"))
      (node (ref "C6") (pin "2") (pinfunction "2_2") (pintype "passive"))
      (node (ref "C7") (pin "2") (pinfunction "2_2") (pintype "passive"))
      (node (ref "D1") (pin "1") (pinfunction "1_1") (pintype "passive"))
      (node (ref "D2") (pin "1") (pinfunction "1_1") (pintype "passive"))
      (node (ref "Q10") (pin "5") (pinfunction "D_5") (pintype "passive"))
      (node (ref "Q10") (pin "6") (pinfunction "D_6") (pintype "passive"))
      (node (ref "Q10") (pin "7") (pinfunction "D_7") (pintype "passive"))
      (node (ref "Q10") (pin "8") (pinfunction "D_8") (pintype "passive"))
      (node (ref "R23") (pin "2") (pinfunction "2_2") (pintype "passive"))
      (node (ref "R29") (pin "1") (pinfunction "1_1") (pintype "passive"))
    )
    (net (code "58") (name "REV-SIG") (class "Default")
      (node (ref "Q6") (pin "1") (pinfunction "COLLECTOR_1") (pintype "passive"))
    )
    (net (code "59") (name "V3.3") (class "Default")
      (node (ref "C19") (pin "1") (pinfunction "1_1") (pintype "passive"))
      (node (ref "L1") (pin "2") (pinfunction "2_2") (pintype "passive"))
      (node (ref "R20") (pin "1") (pinfunction "1_1") (pintype "passive"))
    )
    (net (code "60") (name "V3.3-MCU") (class "Default")
      (node (ref "C4") (pin "2") (pinfunction "2_2") (pintype "passive"))
      (node (ref "U1") (pin "2") (pinfunction "OUT1_2") (pintype "passive"))
      (node (ref "U1") (pin "4") (pinfunction "OUT2_4") (pintype "passive"))
    )
    (net (code "61") (name "V5") (class "Default")
      (node (ref "C29") (pin "1") (pinfunction "1_1") (pintype "passive"))
      (node (ref "L3") (pin "2") (pinfunction "2_2") (pintype "passive"))
      (node (ref "R38") (pin "1") (pinfunction "1_1") (pintype "passive"))
    )
    (net (code "62") (name "V12") (class "Default")
      (node (ref "C18") (pin "2") (pinfunction "2_2") (pintype "passive"))
      (node (ref "C28") (pin "2") (pinfunction "2_2") (pintype "passive"))
      (node (ref "C88") (pin "2") (pinfunction "2_2") (pintype "passive"))
      (node (ref "J2") (pin "2") (pinfunction "2_2") (pintype "passive"))
      (node (ref "Q2") (pin "5") (pinfunction "D_5") (pintype "passive"))
      (node (ref "Q2") (pin "6") (pinfunction "D_6") (pintype "passive"))
      (node (ref "Q2") (pin "7") (pinfunction "D_7") (pintype "passive"))
      (node (ref "Q2") (pin "8") (pinfunction "D_8") (pintype "passive"))
      (node (ref "R18") (pin "2") (pinfunction "2_2") (pintype "passive"))
      (node (ref "R36") (pin "2") (pinfunction "2_2") (pintype "passive"))
      (node (ref "R4") (pin "2") (pinfunction "2_2") (pintype "passive"))
      (node (ref "U3") (pin "2") (pinfunction "IN_2") (pintype "passive"))
      (node (ref "U4") (pin "2") (pinfunction "IN_2") (pintype "passive"))
    )
    (net (code "63") (name "V12-CAM") (class "Default")
      (node (ref "Q1") (pin "5") (pinfunction "D_5") (pintype "passive"))
      (node (ref "Q1") (pin "6") (pinfunction "D_6") (pintype "passive"))
      (node (ref "Q1") (pin "7") (pinfunction "D_7") (pintype "passive"))
      (node (ref "Q1") (pin "8") (pinfunction "D_8") (pintype "passive"))
      (node (ref "R3") (pin "2") (pinfunction "2_2") (pintype "passive"))
    )
    (net (code "64") (name "V12-MP") (class "Default")
      (node (ref "C1") (pin "2") (pinfunction "2_2") (pintype "passive"))
      (node (ref "C10") (pin "1") (pinfunction "1_1") (pintype "passive"))
      (node (ref "C11") (pin "1") (pinfunction "1_1") (pintype "passive"))
      (node (ref "C12") (pin "1") (pinfunction "1_1") (pintype "passive"))
      (node (ref "C13") (pin "1") (pinfunction "1_1") (pintype "passive"))
      (node (ref "C2") (pin "2") (pinfunction "2_2") (pintype "passive"))
      (node (ref "C3") (pin "2") (pinfunction "2_2") (pintype "passive"))
      (node (ref "D10") (pin "2") (pinfunction "K_2") (pintype "passive"))
      (node (ref "Q1") (pin "1") (pinfunction "S_1") (pintype "passive"))
      (node (ref "Q1") (pin "2") (pinfunction "S_2") (pintype "passive"))
      (node (ref "Q1") (pin "3") (pinfunction "S_3") (pintype "passive"))
      (node (ref "Q2") (pin "1") (pinfunction "S_1") (pintype "passive"))
      (node (ref "Q2") (pin "2") (pinfunction "S_2") (pintype "passive"))
      (node (ref "Q2") (pin "3") (pinfunction "S_3") (pintype "passive"))
      (node (ref "Q7") (pin "5") (pinfunction "D_5") (pintype "passive"))
      (node (ref "Q7") (pin "6") (pinfunction "D_6") (pintype "passive"))
      (node (ref "Q7") (pin "7") (pinfunction "D_7") (pintype "passive"))
      (node (ref "Q7") (pin "8") (pinfunction "D_8") (pintype "passive"))
      (node (ref "R1") (pin "2") (pinfunction "2_2") (pintype "passive"))
      (node (ref "R2") (pin "2") (pinfunction "2_2") (pintype "passive"))
      (node (ref "R26") (pin "1") (pinfunction "1_1") (pintype "passive"))
      (node (ref "U1") (pin "3") (pinfunction "IN_3") (pintype "passive"))
    )
    (net (code "65") (name "unconnected-(U2-PGOOD-Pad1)") (class "Default")
      (node (ref "U2") (pin "1") (pinfunction "PGOOD_1") (pintype "passive"))
    )
    (net (code "66") (name "unconnected-(U3-GND-Pad9)") (class "Default")
      (node (ref "U3") (pin "9") (pinfunction "GND_9") (pintype "power_in+no_connect"))
    )
    (net (code "67") (name "unconnected-(U4-GND-Pad9)") (class "Default")
      (node (ref "U4") (pin "9") (pinfunction "GND_9") (pintype "power_in+no_connect"))
    )
  )
)
